# Buzzer.net
KiCad netlist of a schematic drawn in Altium Designer
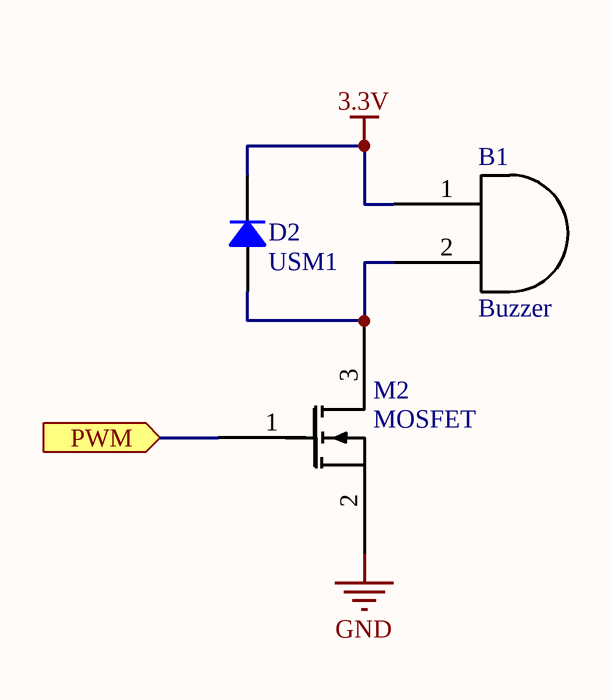
[diagram p0: Buzzer.SchDoc]

(export (version "E")
  (design (tool "Eeschema 10.0.6"))
  (components
    (comp (ref "B1")
      (value "Buzzer")
      (footprint "Buzzer-5050")
      (libsource (lib "Salman_lib") (part "Buzzer"))
    )
    (comp (ref "D2")
      (value "USM1")
      (footprint "DO-214AC SMA")
      (description "Diode Standard 1000V 1A Surface Mount SMA")
      (fields (field (name "PARTNUMBER") "US1M-13-F"))
      (libsource (lib "Diode") (part "US1M (SMD SMA)"))
    )
    (comp (ref "M2") (value "MOSFET") (footprint "SOT-23") (libsource (lib "Salman_lib") (part "2N7002A")))
  )
  (nets
    (net (code "1") (name "/PWM") (class "Default") (node (ref "M2") (pin "1") (pintype "passive")))
    (net (code "2") (name "3.3V") (class "Default")
      (node (ref "B1") (pin "1") (pintype "passive"))
      (node (ref "D2") (pin "2") (pinfunction "2_2") (pintype "passive"))
    )
    (net (code "3") (name "GND") (class "Default") (node (ref "M2") (pin "2") (pintype "passive")))
    (net (code "4") (name "Net-(B1-Pad2)") (class "Default")
      (node (ref "B1") (pin "2") (pintype "passive"))
      (node (ref "D2") (pin "1") (pinfunction "1_1") (pintype "passive"))
      (node (ref "M2") (pin "3") (pintype "passive"))
    )
  )
)
